# RGB_Lamp.net
KiCad netlist of a schematic drawn in EAGLE
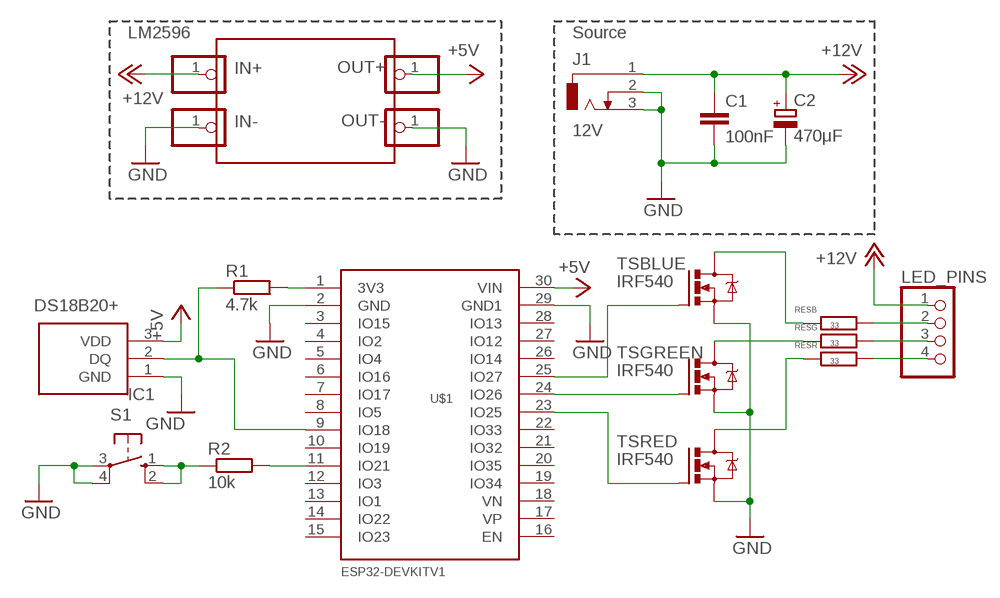
[diagram p0: schematic, sheet 1]

(export (version "E")
  (design (tool "Eeschema 10.0.6"))
  (components
    (comp (ref "C1")
      (value "100nF")
      (footprint "eagle-import:C050-025X075")
      (libsource (lib "eagle-import") (part "C-EU050-025X075"))
    )
    (comp (ref "C2")
      (value "470μF")
      (footprint "eagle-import:E3,5-8")
      (libsource (lib "eagle-import") (part "CPOL-EUE3.5-8"))
    )
    (comp (ref "IC1")
      (value "DS18B20+")
      (footprint "eagle-import:DS18B20")
      (fields (field (name "MOUSER_PART_NUMBER") "700-DS18B20+"))
      (libsource (lib "eagle-import") (part "DS18B20+"))
    )
    (comp (ref "IN+")
      (value "PINHD-1X1")
      (footprint "eagle-import:1X01")
      (libsource (lib "eagle-import") (part "PINHD-1X1"))
    )
    (comp (ref "IN-")
      (value "PINHD-1X1")
      (footprint "eagle-import:1X01")
      (libsource (lib "eagle-import") (part "PINHD-1X1"))
    )
    (comp (ref "J1")
      (value "12V")
      (footprint "eagle-import:DCJ0303")
      (libsource (lib "eagle-import") (part "DCJ0303"))
    )
    (comp (ref "LED_PINS")
      (value "PINHD-1X4")
      (footprint "eagle-import:1X04")
      (libsource (lib "eagle-import") (part "PINHD-1X4"))
    )
    (comp (ref "OUT+")
      (value "PINHD-1X1")
      (footprint "eagle-import:1X01")
      (libsource (lib "eagle-import") (part "PINHD-1X1"))
    )
    (comp (ref "OUT-")
      (value "PINHD-1X1")
      (footprint "eagle-import:1X01")
      (libsource (lib "eagle-import") (part "PINHD-1X1"))
    )
    (comp (ref "R1")
      (value "4.7k")
      (footprint "eagle-import:0207_10")
      (libsource (lib "eagle-import") (part "rcl_334_R-EU_0207/10"))
    )
    (comp (ref "R2")
      (value "10k")
      (footprint "eagle-import:0207_10")
      (libsource (lib "eagle-import") (part "rcl_334_R-EU_0207/10"))
    )
    (comp (ref "RESB")
      (value "33")
      (footprint "eagle-import:0922_22")
      (libsource (lib "eagle-import") (part "R-EU_0922/22"))
    )
    (comp (ref "RESG")
      (value "33")
      (footprint "eagle-import:0922_22")
      (libsource (lib "eagle-import") (part "R-EU_0922/22"))
    )
    (comp (ref "RESR")
      (value "33")
      (footprint "eagle-import:0922_22")
      (libsource (lib "eagle-import") (part "R-EU_0922/22"))
    )
    (comp (ref "S1")
      (value "10-XX")
      (footprint "eagle-import:B3F-10XX")
      (fields (field (name "MPN") "B3F-1000"))
      (libsource (lib "eagle-import") (part "10-XX"))
    )
    (comp (ref "TSBLUE")
      (value "IRF540")
      (footprint "eagle-import:TO220BV")
      (libsource (lib "eagle-import") (part "IRF540"))
    )
    (comp (ref "TSGREEN")
      (value "IRF540")
      (footprint "eagle-import:TO220BV")
      (libsource (lib "eagle-import") (part "IRF540"))
    )
    (comp (ref "TSRED")
      (value "IRF540")
      (footprint "eagle-import:TO220BV")
      (libsource (lib "eagle-import") (part "IRF540"))
    )
    (comp (ref "U$1")
      (value "ESP32DEVKITV1")
      (footprint "eagle-import:ESP32-DEVKITV1")
      (libsource (lib "eagle-import") (part "ESP32DEVKITV1"))
    )
  )
  (nets
    (net (code "1") (name "+5V") (class "Default")
      (node (ref "IC1") (pin "3") (pinfunction "VDD_3") (pintype "bidirectional"))
      (node (ref "OUT+") (pin "1") (pinfunction "1_1") (pintype "passive"))
      (node (ref "U$1") (pin "30") (pinfunction "VIN_30") (pintype "bidirectional"))
    )
    (net (code "2") (name "+12V") (class "Default")
      (node (ref "C1") (pin "1") (pinfunction "1_1") (pintype "passive"))
      (node (ref "C2") (pin "+") (pinfunction "+_+") (pintype "passive"))
      (node (ref "IN+") (pin "1") (pinfunction "1_1") (pintype "passive"))
      (node (ref "J1") (pin "1") (pinfunction "1_1") (pintype "passive"))
      (node (ref "LED_PINS") (pin "1") (pinfunction "1_1") (pintype "passive"))
    )
    (net (code "3") (name "GND") (class "Default")
      (node (ref "C1") (pin "2") (pinfunction "2_2") (pintype "passive"))
      (node (ref "C2") (pin "-") (pinfunction "-_-") (pintype "passive"))
      (node (ref "IC1") (pin "1") (pinfunction "GND_1") (pintype "bidirectional"))
      (node (ref "IN-") (pin "1") (pinfunction "1_1") (pintype "passive"))
      (node (ref "J1") (pin "2") (pinfunction "2_2") (pintype "passive"))
      (node (ref "J1") (pin "3") (pinfunction "3_3") (pintype "passive"))
      (node (ref "OUT-") (pin "1") (pinfunction "1_1") (pintype "passive"))
      (node (ref "S1") (pin "3") (pinfunction "P_3") (pintype "passive"))
      (node (ref "S1") (pin "4") (pinfunction "P1_4") (pintype "passive"))
      (node (ref "TSBLUE") (pin "S") (pinfunction "S_S") (pintype "passive"))
      (node (ref "TSGREEN") (pin "S") (pinfunction "S_S") (pintype "passive"))
      (node (ref "TSRED") (pin "S") (pinfunction "S_S") (pintype "passive"))
      (node (ref "U$1") (pin "2") (pinfunction "GND_2") (pintype "bidirectional"))
      (node (ref "U$1") (pin "29") (pinfunction "GND1_29") (pintype "bidirectional"))
    )
    (net (code "4") (name "Net-(IC1-DQ)") (class "Default")
      (node (ref "IC1") (pin "2") (pinfunction "DQ_2") (pintype "bidirectional"))
      (node (ref "R1") (pin "1") (pinfunction "1_1") (pintype "passive"))
      (node (ref "U$1") (pin "9") (pinfunction "IO18_9") (pintype "bidirectional"))
    )
    (net (code "5") (name "Net-(LED_PINS-Pad2)") (class "Default")
      (node (ref "LED_PINS") (pin "2") (pinfunction "2_2") (pintype "passive"))
      (node (ref "RESB") (pin "2") (pinfunction "2_2") (pintype "passive"))
    )
    (net (code "6") (name "Net-(LED_PINS-Pad3)") (class "Default")
      (node (ref "LED_PINS") (pin "3") (pinfunction "3_3") (pintype "passive"))
      (node (ref "RESG") (pin "2") (pinfunction "2_2") (pintype "passive"))
    )
    (net (code "7") (name "Net-(LED_PINS-Pad4)") (class "Default")
      (node (ref "LED_PINS") (pin "4") (pinfunction "4_4") (pintype "passive"))
      (node (ref "RESR") (pin "2") (pinfunction "2_2") (pintype "passive"))
    )
    (net (code "8") (name "Net-(RESB-Pad1)") (class "Default")
      (node (ref "RESB") (pin "1") (pinfunction "1_1") (pintype "passive"))
      (node (ref "TSBLUE") (pin "D") (pinfunction "D_D") (pintype "passive"))
    )
    (net (code "9") (name "Net-(RESG-Pad1)") (class "Default")
      (node (ref "RESG") (pin "1") (pinfunction "1_1") (pintype "passive"))
      (node (ref "TSGREEN") (pin "D") (pinfunction "D_D") (pintype "passive"))
    )
    (net (code "10") (name "Net-(RESR-Pad1)") (class "Default")
      (node (ref "RESR") (pin "1") (pinfunction "1_1") (pintype "passive"))
      (node (ref "TSRED") (pin "D") (pinfunction "D_D") (pintype "passive"))
    )
    (net (code "11") (name "Net-(S1-S)") (class "Default")
      (node (ref "R2") (pin "1") (pinfunction "1_1") (pintype "passive"))
      (node (ref "S1") (pin "1") (pinfunction "S_1") (pintype "passive"))
      (node (ref "S1") (pin "2") (pinfunction "S1_2") (pintype "passive"))
    )
    (net (code "12") (name "Net-(U$1-3V3)") (class "Default")
      (node (ref "R1") (pin "2") (pinfunction "2_2") (pintype "passive"))
      (node (ref "U$1") (pin "1") (pinfunction "3V3_1") (pintype "bidirectional"))
    )
    (net (code "13") (name "Net-(U$1-IO21)") (class "Default")
      (node (ref "R2") (pin "2") (pinfunction "2_2") (pintype "passive"))
      (node (ref "U$1") (pin "11") (pinfunction "IO21_11") (pintype "bidirectional"))
    )
    (net (code "14") (name "Net-(U$1-IO25)") (class "Default")
      (node (ref "TSRED") (pin "G") (pinfunction "G_G") (pintype "passive"))
      (node (ref "U$1") (pin "23") (pinfunction "IO25_23") (pintype "bidirectional"))
    )
    (net (code "15") (name "Net-(U$1-IO26)") (class "Default")
      (node (ref "TSGREEN") (pin "G") (pinfunction "G_G") (pintype "passive"))
      (node (ref "U$1") (pin "24") (pinfunction "IO26_24") (pintype "bidirectional"))
    )
    (net (code "16") (name "Net-(U$1-IO27)") (class "Default")
      (node (ref "TSBLUE") (pin "G") (pinfunction "G_G") (pintype "passive"))
      (node (ref "U$1") (pin "25") (pinfunction "IO27_25") (pintype "bidirectional"))
    )
    (net (code "17") (name "unconnected-(U$1-EN-Pad16)") (class "Default")
      (node (ref "U$1") (pin "16") (pinfunction "EN_16") (pintype "bidirectional"))
    )
    (net (code "18") (name "unconnected-(U$1-IO1-Pad13)") (class "Default")
      (node (ref "U$1") (pin "13") (pinfunction "IO1_13") (pintype "bidirectional"))
    )
    (net (code "19") (name "unconnected-(U$1-IO2-Pad4)") (class "Default")
      (node (ref "U$1") (pin "4") (pinfunction "IO2_4") (pintype "bidirectional"))
    )
    (net (code "20") (name "unconnected-(U$1-IO3-Pad12)") (class "Default")
      (node (ref "U$1") (pin "12") (pinfunction "IO3_12") (pintype "bidirectional"))
    )
    (net (code "21") (name "unconnected-(U$1-IO4-Pad5)") (class "Default")
      (node (ref "U$1") (pin "5") (pinfunction "IO4_5") (pintype "bidirectional"))
    )
    (net (code "22") (name "unconnected-(U$1-IO5-Pad8)") (class "Default")
      (node (ref "U$1") (pin "8") (pinfunction "IO5_8") (pintype "bidirectional"))
    )
    (net (code "23") (name "unconnected-(U$1-IO12-Pad27)") (class "Default")
      (node (ref "U$1") (pin "27") (pinfunction "IO12_27") (pintype "bidirectional"))
    )
    (net (code "24") (name "unconnected-(U$1-IO13-Pad28)") (class "Default")
      (node (ref "U$1") (pin "28") (pinfunction "IO13_28") (pintype "bidirectional"))
    )
    (net (code "25") (name "unconnected-(U$1-IO14-Pad26)") (class "Default")
      (node (ref "U$1") (pin "26") (pinfunction "IO14_26") (pintype "bidirectional"))
    )
    (net (code "26") (name "unconnected-(U$1-IO15-Pad3)") (class "Default")
      (node (ref "U$1") (pin "3") (pinfunction "IO15_3") (pintype "bidirectional"))
    )
    (net (code "27") (name "unconnected-(U$1-IO16-Pad6)") (class "Default")
      (node (ref "U$1") (pin "6") (pinfunction "IO16_6") (pintype "bidirectional"))
    )
    (net (code "28") (name "unconnected-(U$1-IO17-Pad7)") (class "Default")
      (node (ref "U$1") (pin "7") (pinfunction "IO17_7") (pintype "bidirectional"))
    )
    (net (code "29") (name "unconnected-(U$1-IO19-Pad10)") (class "Default")
      (node (ref "U$1") (pin "10") (pinfunction "IO19_10") (pintype "bidirectional"))
    )
    (net (code "30") (name "unconnected-(U$1-IO22-Pad14)") (class "Default")
      (node (ref "U$1") (pin "14") (pinfunction "IO22_14") (pintype "bidirectional"))
    )
    (net (code "31") (name "unconnected-(U$1-IO23-Pad15)") (class "Default")
      (node (ref "U$1") (pin "15") (pinfunction "IO23_15") (pintype "bidirectional"))
    )
    (net (code "32") (name "unconnected-(U$1-IO32-Pad21)") (class "Default")
      (node (ref "U$1") (pin "21") (pinfunction "IO32_21") (pintype "bidirectional"))
    )
    (net (code "33") (name "unconnected-(U$1-IO33-Pad22)") (class "Default")
      (node (ref "U$1") (pin "22") (pinfunction "IO33_22") (pintype "bidirectional"))
    )
    (net (code "34") (name "unconnected-(U$1-IO34-Pad19)") (class "Default")
      (node (ref "U$1") (pin "19") (pinfunction "IO34_19") (pintype "bidirectional"))
    )
    (net (code "35") (name "unconnected-(U$1-IO35-Pad20)") (class "Default")
      (node (ref "U$1") (pin "20") (pinfunction "IO35_20") (pintype "bidirectional"))
    )
    (net (code "36") (name "unconnected-(U$1-VN-Pad18)") (class "Default")
      (node (ref "U$1") (pin "18") (pinfunction "VN_18") (pintype "bidirectional"))
    )
    (net (code "37") (name "unconnected-(U$1-VP-Pad17)") (class "Default")
      (node (ref "U$1") (pin "17") (pinfunction "VP_17") (pintype "bidirectional"))
    )
  )
)
